# AC-CTRL-BRD.net
KiCad netlist of a schematic drawn in EAGLE
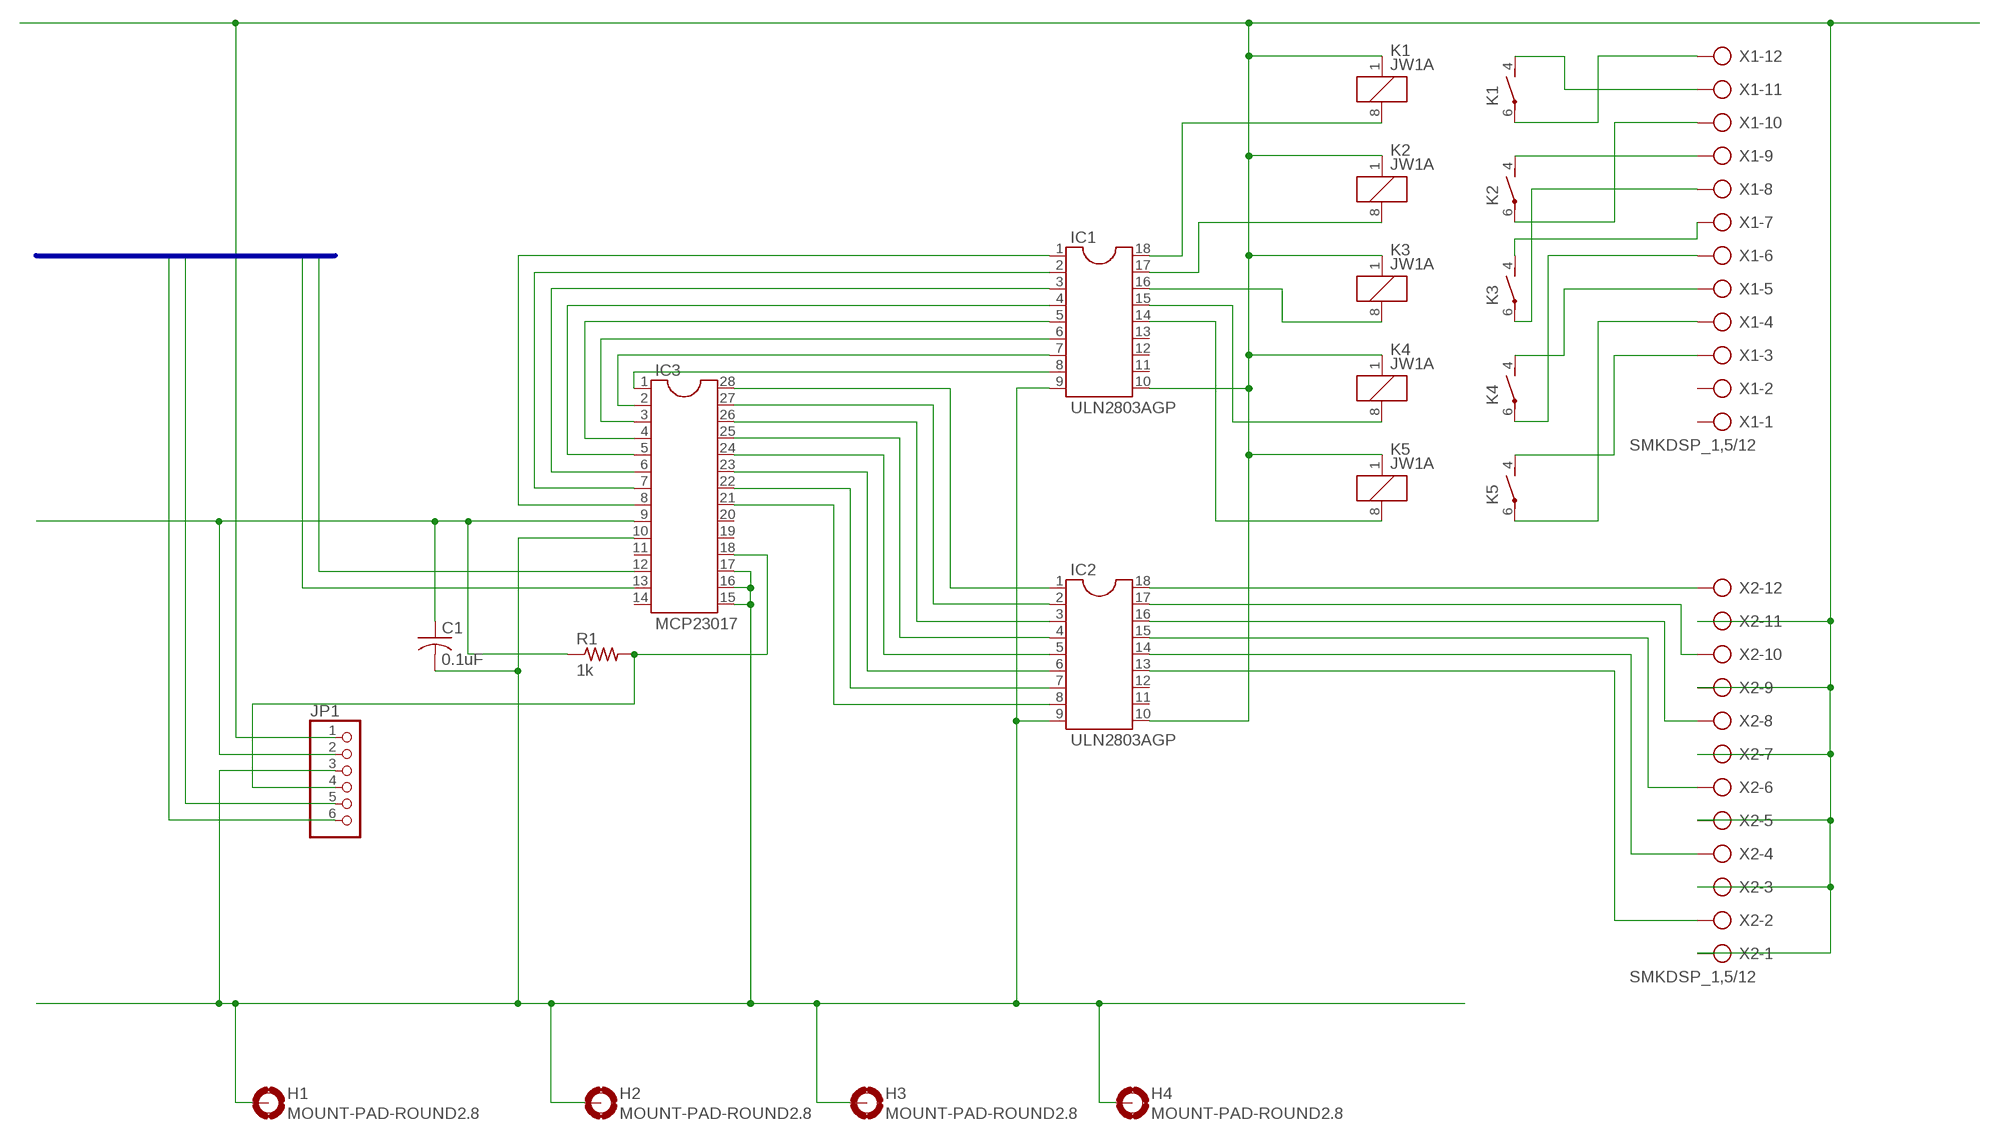
[diagram p0: schematic, sheet 1]

(export (version "E")
  (design (tool "Eeschema 10.0.6"))
  (components
    (comp (ref "C1")
      (value "0.1uF")
      (footprint "eagle-import:C050-024X044")
      (libsource (lib "eagle-import") (part "C-US050-024X044"))
    )
    (comp (ref "H1")
      (value "MOUNT-PAD-ROUND2.8")
      (footprint "eagle-import:2,8-PAD")
      (libsource (lib "eagle-import") (part "MOUNT-PAD-ROUND2.8"))
    )
    (comp (ref "H2")
      (value "MOUNT-PAD-ROUND2.8")
      (footprint "eagle-import:2,8-PAD")
      (libsource (lib "eagle-import") (part "MOUNT-PAD-ROUND2.8"))
    )
    (comp (ref "H3")
      (value "MOUNT-PAD-ROUND2.8")
      (footprint "eagle-import:2,8-PAD")
      (libsource (lib "eagle-import") (part "MOUNT-PAD-ROUND2.8"))
    )
    (comp (ref "H4")
      (value "MOUNT-PAD-ROUND2.8")
      (footprint "eagle-import:2,8-PAD")
      (libsource (lib "eagle-import") (part "MOUNT-PAD-ROUND2.8"))
    )
    (comp (ref "IC1")
      (value "ULN2803AGP")
      (footprint "eagle-import:DIL18")
      (libsource (lib "eagle-import") (part "DIL18"))
    )
    (comp (ref "IC2")
      (value "ULN2803AGP")
      (footprint "eagle-import:DIL18")
      (libsource (lib "eagle-import") (part "DIL18"))
    )
    (comp (ref "IC3")
      (value "MCP23017")
      (footprint "eagle-import:DIL28-3")
      (libsource (lib "eagle-import") (part "DIL28-3"))
    )
    (comp (ref "JP1")
      (value "PINHD-1X6")
      (footprint "eagle-import:1X06")
      (libsource (lib "eagle-import") (part "PINHD-1X6"))
    )
    (comp (ref "K1")
      (value "JW1A")
      (footprint "eagle-import:JW1A")
      (libsource (lib "eagle-import") (part "JW1A"))
    )
    (comp (ref "K2")
      (value "JW1A")
      (footprint "eagle-import:JW1A")
      (libsource (lib "eagle-import") (part "JW1A"))
    )
    (comp (ref "K3")
      (value "JW1A")
      (footprint "eagle-import:JW1A")
      (libsource (lib "eagle-import") (part "JW1A"))
    )
    (comp (ref "K4")
      (value "JW1A")
      (footprint "eagle-import:JW1A")
      (libsource (lib "eagle-import") (part "JW1A"))
    )
    (comp (ref "K5")
      (value "JW1A")
      (footprint "eagle-import:JW1A")
      (libsource (lib "eagle-import") (part "JW1A"))
    )
    (comp (ref "R1")
      (value "1k")
      (footprint "eagle-import:0204_7")
      (libsource (lib "eagle-import") (part "R-US_0204/7"))
    )
    (comp (ref "X1")
      (value "SMKDSP_1,5/12")
      (footprint "eagle-import:SMKDSP_1,5_12")
      (libsource (lib "eagle-import") (part "SMKDSP_1,5/12"))
    )
    (comp (ref "X2")
      (value "SMKDSP_1,5/12")
      (footprint "eagle-import:SMKDSP_1,5_12")
      (libsource (lib "eagle-import") (part "SMKDSP_1,5/12"))
    )
  )
  (nets
    (net (code "1") (name "/SCL") (class "Default")
      (node (ref "IC3") (pin "12") (pinfunction "12_12") (pintype "passive"))
      (node (ref "JP1") (pin "6") (pinfunction "6_6") (pintype "passive"))
    )
    (net (code "2") (name "/SDA") (class "Default")
      (node (ref "IC3") (pin "13") (pinfunction "13_13") (pintype "passive"))
      (node (ref "JP1") (pin "5") (pinfunction "5_5") (pintype "passive"))
    )
    (net (code "3") (name "Net-(C1-Pad1)") (class "Default")
      (node (ref "C1") (pin "1") (pinfunction "1_1") (pintype "passive"))
      (node (ref "IC3") (pin "9") (pinfunction "9_9") (pintype "passive"))
      (node (ref "JP1") (pin "2") (pinfunction "2_2") (pintype "passive"))
      (node (ref "R1") (pin "1") (pinfunction "1_1") (pintype "passive"))
    )
    (net (code "4") (name "Net-(H1-MOUNT)") (class "Default")
      (node (ref "C1") (pin "2") (pinfunction "2_2") (pintype "passive"))
      (node (ref "H1") (pin "B2,8") (pinfunction "MOUNT_B2,8") (pintype "passive"))
      (node (ref "H2") (pin "B2,8") (pinfunction "MOUNT_B2,8") (pintype "passive"))
      (node (ref "H3") (pin "B2,8") (pinfunction "MOUNT_B2,8") (pintype "passive"))
      (node (ref "H4") (pin "B2,8") (pinfunction "MOUNT_B2,8") (pintype "passive"))
      (node (ref "IC1") (pin "9") (pinfunction "9_9") (pintype "passive"))
      (node (ref "IC2") (pin "9") (pinfunction "9_9") (pintype "passive"))
      (node (ref "IC3") (pin "10") (pinfunction "10_10") (pintype "passive"))
      (node (ref "IC3") (pin "15") (pinfunction "15_15") (pintype "passive"))
      (node (ref "IC3") (pin "16") (pinfunction "16_16") (pintype "passive"))
      (node (ref "IC3") (pin "17") (pinfunction "17_17") (pintype "passive"))
      (node (ref "JP1") (pin "3") (pinfunction "3_3") (pintype "passive"))
    )
    (net (code "5") (name "Net-(IC1-Pad1)") (class "Default")
      (node (ref "IC1") (pin "1") (pinfunction "1_1") (pintype "passive"))
      (node (ref "IC3") (pin "8") (pinfunction "8_8") (pintype "passive"))
    )
    (net (code "6") (name "Net-(IC1-Pad2)") (class "Default")
      (node (ref "IC1") (pin "2") (pinfunction "2_2") (pintype "passive"))
      (node (ref "IC3") (pin "7") (pinfunction "7_7") (pintype "passive"))
    )
    (net (code "7") (name "Net-(IC1-Pad3)") (class "Default")
      (node (ref "IC1") (pin "3") (pinfunction "3_3") (pintype "passive"))
      (node (ref "IC3") (pin "6") (pinfunction "6_6") (pintype "passive"))
    )
    (net (code "8") (name "Net-(IC1-Pad4)") (class "Default")
      (node (ref "IC1") (pin "4") (pinfunction "4_4") (pintype "passive"))
      (node (ref "IC3") (pin "5") (pinfunction "5_5") (pintype "passive"))
    )
    (net (code "9") (name "Net-(IC1-Pad5)") (class "Default")
      (node (ref "IC1") (pin "5") (pinfunction "5_5") (pintype "passive"))
      (node (ref "IC3") (pin "4") (pinfunction "4_4") (pintype "passive"))
    )
    (net (code "10") (name "Net-(IC1-Pad6)") (class "Default")
      (node (ref "IC1") (pin "6") (pinfunction "6_6") (pintype "passive"))
      (node (ref "IC3") (pin "3") (pinfunction "3_3") (pintype "passive"))
    )
    (net (code "11") (name "Net-(IC1-Pad7)") (class "Default")
      (node (ref "IC1") (pin "7") (pinfunction "7_7") (pintype "passive"))
      (node (ref "IC3") (pin "2") (pinfunction "2_2") (pintype "passive"))
    )
    (net (code "12") (name "Net-(IC1-Pad8)") (class "Default")
      (node (ref "IC1") (pin "8") (pinfunction "8_8") (pintype "passive"))
      (node (ref "IC3") (pin "1") (pinfunction "1_1") (pintype "passive"))
    )
    (net (code "13") (name "Net-(IC2-Pad1)") (class "Default")
      (node (ref "IC2") (pin "1") (pinfunction "1_1") (pintype "passive"))
      (node (ref "IC3") (pin "28") (pinfunction "28_28") (pintype "passive"))
    )
    (net (code "14") (name "Net-(IC2-Pad2)") (class "Default")
      (node (ref "IC2") (pin "2") (pinfunction "2_2") (pintype "passive"))
      (node (ref "IC3") (pin "27") (pinfunction "27_27") (pintype "passive"))
    )
    (net (code "15") (name "Net-(IC2-Pad3)") (class "Default")
      (node (ref "IC2") (pin "3") (pinfunction "3_3") (pintype "passive"))
      (node (ref "IC3") (pin "26") (pinfunction "26_26") (pintype "passive"))
    )
    (net (code "16") (name "Net-(IC2-Pad4)") (class "Default")
      (node (ref "IC2") (pin "4") (pinfunction "4_4") (pintype "passive"))
      (node (ref "IC3") (pin "25") (pinfunction "25_25") (pintype "passive"))
    )
    (net (code "17") (name "Net-(IC2-Pad5)") (class "Default")
      (node (ref "IC2") (pin "5") (pinfunction "5_5") (pintype "passive"))
      (node (ref "IC3") (pin "24") (pinfunction "24_24") (pintype "passive"))
    )
    (net (code "18") (name "Net-(IC2-Pad6)") (class "Default")
      (node (ref "IC2") (pin "6") (pinfunction "6_6") (pintype "passive"))
      (node (ref "IC3") (pin "23") (pinfunction "23_23") (pintype "passive"))
    )
    (net (code "19") (name "Net-(IC2-Pad7)") (class "Default")
      (node (ref "IC2") (pin "7") (pinfunction "7_7") (pintype "passive"))
      (node (ref "IC3") (pin "22") (pinfunction "22_22") (pintype "passive"))
    )
    (net (code "20") (name "Net-(IC2-Pad8)") (class "Default")
      (node (ref "IC2") (pin "8") (pinfunction "8_8") (pintype "passive"))
      (node (ref "IC3") (pin "21") (pinfunction "21_21") (pintype "passive"))
    )
    (net (code "21") (name "Net-(IC3-Pad18)") (class "Default")
      (node (ref "IC3") (pin "18") (pinfunction "18_18") (pintype "passive"))
      (node (ref "JP1") (pin "4") (pinfunction "4_4") (pintype "passive"))
      (node (ref "R1") (pin "2") (pinfunction "2_2") (pintype "passive"))
    )
    (net (code "22") (name "Net-(K1A-P)") (class "Default")
      (node (ref "K1") (pin "6") (pinfunction "P_6") (pintype "passive"))
      (node (ref "X1") (pin "12") (pinfunction "KL_12") (pintype "passive"))
    )
    (net (code "23") (name "Net-(K1A-S)") (class "Default")
      (node (ref "K1") (pin "4") (pinfunction "S_4") (pintype "passive"))
      (node (ref "X1") (pin "11") (pinfunction "KL_11") (pintype "passive"))
    )
    (net (code "24") (name "Net-(K1B-2)") (class "Default")
      (node (ref "IC1") (pin "18") (pinfunction "18_18") (pintype "passive"))
      (node (ref "K1") (pin "8") (pinfunction "2_8") (pintype "passive"))
    )
    (net (code "25") (name "Net-(K2A-P)") (class "Default")
      (node (ref "K2") (pin "6") (pinfunction "P_6") (pintype "passive"))
      (node (ref "X1") (pin "10") (pinfunction "KL_10") (pintype "passive"))
    )
    (net (code "26") (name "Net-(K2A-S)") (class "Default")
      (node (ref "K2") (pin "4") (pinfunction "S_4") (pintype "passive"))
      (node (ref "X1") (pin "9") (pinfunction "KL_9") (pintype "passive"))
    )
    (net (code "27") (name "Net-(K2B-2)") (class "Default")
      (node (ref "IC1") (pin "17") (pinfunction "17_17") (pintype "passive"))
      (node (ref "K2") (pin "8") (pinfunction "2_8") (pintype "passive"))
    )
    (net (code "28") (name "Net-(K3A-P)") (class "Default")
      (node (ref "K3") (pin "6") (pinfunction "P_6") (pintype "passive"))
      (node (ref "X1") (pin "8") (pinfunction "KL_8") (pintype "passive"))
    )
    (net (code "29") (name "Net-(K3A-S)") (class "Default")
      (node (ref "K3") (pin "4") (pinfunction "S_4") (pintype "passive"))
      (node (ref "X1") (pin "7") (pinfunction "KL_7") (pintype "passive"))
    )
    (net (code "30") (name "Net-(K3B-2)") (class "Default")
      (node (ref "IC1") (pin "16") (pinfunction "16_16") (pintype "passive"))
      (node (ref "K3") (pin "8") (pinfunction "2_8") (pintype "passive"))
    )
    (net (code "31") (name "Net-(K4A-P)") (class "Default")
      (node (ref "K4") (pin "6") (pinfunction "P_6") (pintype "passive"))
      (node (ref "X1") (pin "6") (pinfunction "KL_6") (pintype "passive"))
    )
    (net (code "32") (name "Net-(K4A-S)") (class "Default")
      (node (ref "K4") (pin "4") (pinfunction "S_4") (pintype "passive"))
      (node (ref "X1") (pin "5") (pinfunction "KL_5") (pintype "passive"))
    )
    (net (code "33") (name "Net-(K4B-2)") (class "Default")
      (node (ref "IC1") (pin "15") (pinfunction "15_15") (pintype "passive"))
      (node (ref "K4") (pin "8") (pinfunction "2_8") (pintype "passive"))
    )
    (net (code "34") (name "Net-(K5A-P)") (class "Default")
      (node (ref "K5") (pin "6") (pinfunction "P_6") (pintype "passive"))
      (node (ref "X1") (pin "4") (pinfunction "KL_4") (pintype "passive"))
    )
    (net (code "35") (name "Net-(K5A-S)") (class "Default")
      (node (ref "K5") (pin "4") (pinfunction "S_4") (pintype "passive"))
      (node (ref "X1") (pin "3") (pinfunction "KL_3") (pintype "passive"))
    )
    (net (code "36") (name "Net-(K5B-2)") (class "Default")
      (node (ref "IC1") (pin "14") (pinfunction "14_14") (pintype "passive"))
      (node (ref "K5") (pin "8") (pinfunction "2_8") (pintype "passive"))
    )
    (net (code "37") (name "Net-(X2A-KL)") (class "Default")
      (node (ref "IC1") (pin "10") (pinfunction "10_10") (pintype "passive"))
      (node (ref "IC2") (pin "10") (pinfunction "10_10") (pintype "passive"))
      (node (ref "JP1") (pin "1") (pinfunction "1_1") (pintype "passive"))
      (node (ref "K1") (pin "1") (pinfunction "1_1") (pintype "passive"))
      (node (ref "K2") (pin "1") (pinfunction "1_1") (pintype "passive"))
      (node (ref "K3") (pin "1") (pinfunction "1_1") (pintype "passive"))
      (node (ref "K4") (pin "1") (pinfunction "1_1") (pintype "passive"))
      (node (ref "K5") (pin "1") (pinfunction "1_1") (pintype "passive"))
      (node (ref "X2") (pin "1") (pinfunction "KL_1") (pintype "passive"))
      (node (ref "X2") (pin "11") (pinfunction "KL_11") (pintype "passive"))
      (node (ref "X2") (pin "3") (pinfunction "KL_3") (pintype "passive"))
      (node (ref "X2") (pin "5") (pinfunction "KL_5") (pintype "passive"))
      (node (ref "X2") (pin "7") (pinfunction "KL_7") (pintype "passive"))
      (node (ref "X2") (pin "9") (pinfunction "KL_9") (pintype "passive"))
    )
    (net (code "38") (name "Net-(X2B-KL)") (class "Default")
      (node (ref "IC2") (pin "17") (pinfunction "17_17") (pintype "passive"))
      (node (ref "X2") (pin "10") (pinfunction "KL_10") (pintype "passive"))
    )
    (net (code "39") (name "Net-(X2D-KL)") (class "Default")
      (node (ref "IC2") (pin "18") (pinfunction "18_18") (pintype "passive"))
      (node (ref "X2") (pin "12") (pinfunction "KL_12") (pintype "passive"))
    )
    (net (code "40") (name "Net-(X2E-KL)") (class "Default")
      (node (ref "IC2") (pin "13") (pinfunction "13_13") (pintype "passive"))
      (node (ref "X2") (pin "2") (pinfunction "KL_2") (pintype "passive"))
    )
    (net (code "41") (name "Net-(X2G-KL)") (class "Default")
      (node (ref "IC2") (pin "14") (pinfunction "14_14") (pintype "passive"))
      (node (ref "X2") (pin "4") (pinfunction "KL_4") (pintype "passive"))
    )
    (net (code "42") (name "Net-(X2I-KL)") (class "Default")
      (node (ref "IC2") (pin "15") (pinfunction "15_15") (pintype "passive"))
      (node (ref "X2") (pin "6") (pinfunction "KL_6") (pintype "passive"))
    )
    (net (code "43") (name "Net-(X2K-KL)") (class "Default")
      (node (ref "IC2") (pin "16") (pinfunction "16_16") (pintype "passive"))
      (node (ref "X2") (pin "8") (pinfunction "KL_8") (pintype "passive"))
    )
    (net (code "44") (name "unconnected-(IC1-Pad11)") (class "Default")
      (node (ref "IC1") (pin "11") (pinfunction "11_11") (pintype "passive"))
    )
    (net (code "45") (name "unconnected-(IC1-Pad12)") (class "Default")
      (node (ref "IC1") (pin "12") (pinfunction "12_12") (pintype "passive"))
    )
    (net (code "46") (name "unconnected-(IC1-Pad13)") (class "Default")
      (node (ref "IC1") (pin "13") (pinfunction "13_13") (pintype "passive"))
    )
    (net (code "47") (name "unconnected-(IC2-Pad11)") (class "Default")
      (node (ref "IC2") (pin "11") (pinfunction "11_11") (pintype "passive"))
    )
    (net (code "48") (name "unconnected-(IC2-Pad12)") (class "Default")
      (node (ref "IC2") (pin "12") (pinfunction "12_12") (pintype "passive"))
    )
    (net (code "49") (name "unconnected-(IC3-Pad11)") (class "Default")
      (node (ref "IC3") (pin "11") (pinfunction "11_11") (pintype "passive"))
    )
    (net (code "50") (name "unconnected-(IC3-Pad14)") (class "Default")
      (node (ref "IC3") (pin "14") (pinfunction "14_14") (pintype "passive"))
    )
    (net (code "51") (name "unconnected-(IC3-Pad19)") (class "Default")
      (node (ref "IC3") (pin "19") (pinfunction "19_19") (pintype "passive"))
    )
    (net (code "52") (name "unconnected-(IC3-Pad20)") (class "Default")
      (node (ref "IC3") (pin "20") (pinfunction "20_20") (pintype "passive"))
    )
    (net (code "53") (name "unconnected-(X1A-KL-Pad1)") (class "Default")
      (node (ref "X1") (pin "1") (pinfunction "KL_1") (pintype "passive"))
    )
    (net (code "54") (name "unconnected-(X1E-KL-Pad2)") (class "Default")
      (node (ref "X1") (pin "2") (pinfunction "KL_2") (pintype "passive"))
    )
  )
)
